# ESP32.net
KiCad netlist of a schematic drawn in EAGLE
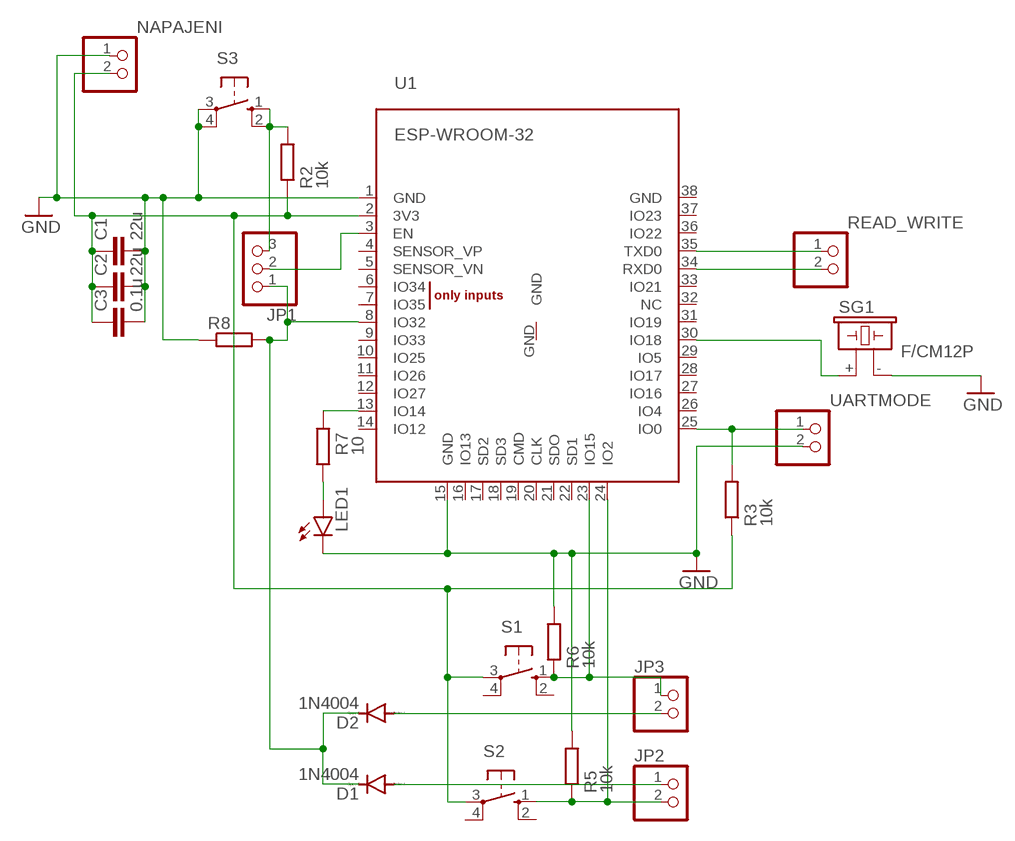
[diagram p0: schematic, sheet 1]

(export (version "E")
  (design (tool "Eeschema 10.0.6"))
  (components
    (comp (ref "C1")
      (value "22u")
      (footprint "eagle-import:C2.5-2")
      (libsource (lib "eagle-import") (part "C2.5/2"))
    )
    (comp (ref "C2")
      (value "22u")
      (footprint "eagle-import:C2.5-2")
      (libsource (lib "eagle-import") (part "C2.5/2"))
    )
    (comp (ref "C3")
      (value "0.1u")
      (footprint "eagle-import:C2.5-2")
      (libsource (lib "eagle-import") (part "C2.5/2"))
    )
    (comp (ref "D1")
      (value "1N4004")
      (footprint "eagle-import:DO41-10")
      (libsource (lib "eagle-import") (part "1N4004"))
    )
    (comp (ref "D2")
      (value "1N4004")
      (footprint "eagle-import:DO41-10")
      (libsource (lib "eagle-import") (part "1N4004"))
    )
    (comp (ref "JP1")
      (value "PINHD-1X3")
      (footprint "eagle-import:1X03")
      (libsource (lib "eagle-import") (part "PINHD-1X3"))
    )
    (comp (ref "JP2")
      (value "PINHD-1X2")
      (footprint "eagle-import:1X02")
      (libsource (lib "eagle-import") (part "PINHD-1X2"))
    )
    (comp (ref "JP3")
      (value "PINHD-1X2")
      (footprint "eagle-import:1X02")
      (libsource (lib "eagle-import") (part "PINHD-1X2"))
    )
    (comp (ref "LED1")
      (value "LED5MM")
      (footprint "eagle-import:LED5MM")
      (libsource (lib "eagle-import") (part "LED5MM"))
    )
    (comp (ref "NAPAJENI")
      (value "PINHD-1X2")
      (footprint "eagle-import:1X02")
      (libsource (lib "eagle-import") (part "PINHD-1X2"))
    )
    (comp (ref "R2")
      (value "10k")
      (footprint "eagle-import:0207_10")
      (libsource (lib "eagle-import") (part "R-EU_0207/10"))
    )
    (comp (ref "R3")
      (value "10k")
      (footprint "eagle-import:0207_10")
      (libsource (lib "eagle-import") (part "R-EU_0207/10"))
    )
    (comp (ref "R5")
      (value "10k")
      (footprint "eagle-import:0207_10")
      (libsource (lib "eagle-import") (part "R-EU_0207/10"))
    )
    (comp (ref "R6")
      (value "10k")
      (footprint "eagle-import:0207_10")
      (libsource (lib "eagle-import") (part "R-EU_0207/10"))
    )
    (comp (ref "R7")
      (value "10")
      (footprint "eagle-import:0207_10")
      (libsource (lib "eagle-import") (part "R-EU_0207/10"))
    )
    (comp (ref "R8")
      (value "R-EU_0207/10")
      (footprint "eagle-import:0207_10")
      (libsource (lib "eagle-import") (part "R-EU_0207/10"))
    )
    (comp (ref "READ_WRITE")
      (value "PINHD-1X2")
      (footprint "eagle-import:1X02")
      (libsource (lib "eagle-import") (part "PINHD-1X2"))
    )
    (comp (ref "S1")
      (value "10-XX")
      (footprint "eagle-import:B3F-10XX")
      (fields (field (name "MPN") "B3F-1000"))
      (libsource (lib "eagle-import") (part "10-XX"))
    )
    (comp (ref "S2")
      (value "10-XX")
      (footprint "eagle-import:B3F-10XX")
      (fields (field (name "MPN") "B3F-1000"))
      (libsource (lib "eagle-import") (part "10-XX"))
    )
    (comp (ref "S3")
      (value "10-XX")
      (footprint "eagle-import:B3F-10XX")
      (fields (field (name "MPN") "B3F-1000"))
      (libsource (lib "eagle-import") (part "10-XX"))
    )
    (comp (ref "SG1")
      (value "F/CM12P")
      (footprint "eagle-import:F_CM12P")
      (libsource (lib "eagle-import") (part "F/CM12P"))
    )
    (comp (ref "U1")
      (value "ESP-WROOM-32")
      (footprint "eagle-import:ESP-WROOM-32")
      (libsource (lib "eagle-import") (part "ESP-WROOM-32"))
    )
    (comp (ref "UARTMODE")
      (value "PINHD-1X2")
      (footprint "eagle-import:1X02")
      (libsource (lib "eagle-import") (part "PINHD-1X2"))
    )
  )
  (nets
    (net (code "1") (name "GND") (class "Default")
      (node (ref "C1") (pin "2") (pinfunction "2_2") (pintype "passive"))
      (node (ref "C2") (pin "2") (pinfunction "2_2") (pintype "passive"))
      (node (ref "C3") (pin "2") (pinfunction "2_2") (pintype "passive"))
      (node (ref "LED1") (pin "K") (pinfunction "C_K") (pintype "passive"))
      (node (ref "NAPAJENI") (pin "1") (pinfunction "1_1") (pintype "passive"))
      (node (ref "R5") (pin "2") (pinfunction "2_2") (pintype "passive"))
      (node (ref "R6") (pin "2") (pinfunction "2_2") (pintype "passive"))
      (node (ref "R8") (pin "1") (pinfunction "1_1") (pintype "passive"))
      (node (ref "S3") (pin "3") (pinfunction "P_3") (pintype "passive"))
      (node (ref "S3") (pin "4") (pinfunction "P1_4") (pintype "passive"))
      (node (ref "SG1") (pin "-") (pinfunction "2_-") (pintype "passive"))
      (node (ref "U1") (pin "1") (pinfunction "GND_1") (pintype "bidirectional"))
      (node (ref "U1") (pin "15") (pinfunction "GND_15") (pintype "bidirectional"))
      (node (ref "UARTMODE") (pin "2") (pinfunction "2_2") (pintype "passive"))
    )
    (net (code "2") (name "Net-(D1-PadA)") (class "Default")
      (node (ref "D1") (pin "A") (pinfunction "A_A") (pintype "passive"))
      (node (ref "JP2") (pin "1") (pinfunction "1_1") (pintype "passive"))
    )
    (net (code "3") (name "Net-(D2-PadA)") (class "Default")
      (node (ref "D2") (pin "A") (pinfunction "A_A") (pintype "passive"))
      (node (ref "JP3") (pin "2") (pinfunction "2_2") (pintype "passive"))
    )
    (net (code "4") (name "Net-(LED1-PadA)") (class "Default")
      (node (ref "LED1") (pin "A") (pinfunction "A_A") (pintype "passive"))
      (node (ref "R7") (pin "1") (pinfunction "1_1") (pintype "passive"))
    )
    (net (code "5") (name "Net-(S1-P)") (class "Default")
      (node (ref "C1") (pin "1") (pinfunction "1_1") (pintype "passive"))
      (node (ref "C2") (pin "1") (pinfunction "1_1") (pintype "passive"))
      (node (ref "C3") (pin "1") (pinfunction "1_1") (pintype "passive"))
      (node (ref "NAPAJENI") (pin "2") (pinfunction "2_2") (pintype "passive"))
      (node (ref "R2") (pin "1") (pinfunction "1_1") (pintype "passive"))
      (node (ref "R3") (pin "1") (pinfunction "1_1") (pintype "passive"))
      (node (ref "S1") (pin "3") (pinfunction "P_3") (pintype "passive"))
      (node (ref "S2") (pin "3") (pinfunction "P_3") (pintype "passive"))
      (node (ref "U1") (pin "2") (pinfunction "3V3_2") (pintype "bidirectional"))
    )
    (net (code "6") (name "Net-(S1-S)") (class "Default")
      (node (ref "JP3") (pin "1") (pinfunction "1_1") (pintype "passive"))
      (node (ref "R6") (pin "1") (pinfunction "1_1") (pintype "passive"))
      (node (ref "S1") (pin "1") (pinfunction "S_1") (pintype "passive"))
      (node (ref "U1") (pin "23") (pinfunction "IO15_23") (pintype "bidirectional"))
    )
    (net (code "7") (name "Net-(S2-S)") (class "Default")
      (node (ref "JP2") (pin "2") (pinfunction "2_2") (pintype "passive"))
      (node (ref "R5") (pin "1") (pinfunction "1_1") (pintype "passive"))
      (node (ref "S2") (pin "1") (pinfunction "S_1") (pintype "passive"))
      (node (ref "U1") (pin "24") (pinfunction "IO2_24") (pintype "bidirectional"))
    )
    (net (code "8") (name "Net-(S3-S)") (class "Default")
      (node (ref "JP1") (pin "3") (pinfunction "3_3") (pintype "passive"))
      (node (ref "R2") (pin "2") (pinfunction "2_2") (pintype "passive"))
      (node (ref "S3") (pin "1") (pinfunction "S_1") (pintype "passive"))
      (node (ref "S3") (pin "2") (pinfunction "S1_2") (pintype "passive"))
    )
    (net (code "9") (name "Net-(SG1-1)") (class "Default")
      (node (ref "SG1") (pin "+") (pinfunction "1_+") (pintype "passive"))
      (node (ref "U1") (pin "30") (pinfunction "IO18_30") (pintype "bidirectional"))
    )
    (net (code "10") (name "Net-(U1-EN)") (class "Default")
      (node (ref "JP1") (pin "2") (pinfunction "2_2") (pintype "passive"))
      (node (ref "U1") (pin "3") (pinfunction "EN_3") (pintype "bidirectional"))
    )
    (net (code "11") (name "Net-(U1-IO0)") (class "Default")
      (node (ref "R3") (pin "2") (pinfunction "2_2") (pintype "passive"))
      (node (ref "U1") (pin "25") (pinfunction "IO0_25") (pintype "bidirectional"))
      (node (ref "UARTMODE") (pin "1") (pinfunction "1_1") (pintype "passive"))
    )
    (net (code "12") (name "Net-(U1-IO14)") (class "Default")
      (node (ref "R7") (pin "2") (pinfunction "2_2") (pintype "passive"))
      (node (ref "U1") (pin "13") (pinfunction "IO14_13") (pintype "bidirectional"))
    )
    (net (code "13") (name "Net-(U1-IO32)") (class "Default")
      (node (ref "D1") (pin "C") (pinfunction "C_C") (pintype "passive"))
      (node (ref "D2") (pin "C") (pinfunction "C_C") (pintype "passive"))
      (node (ref "JP1") (pin "1") (pinfunction "1_1") (pintype "passive"))
      (node (ref "R8") (pin "2") (pinfunction "2_2") (pintype "passive"))
      (node (ref "U1") (pin "8") (pinfunction "IO32_8") (pintype "bidirectional"))
    )
    (net (code "14") (name "Net-(U1-RXD0)") (class "Default")
      (node (ref "READ_WRITE") (pin "2") (pinfunction "2_2") (pintype "passive"))
      (node (ref "U1") (pin "34") (pinfunction "RXD0_34") (pintype "bidirectional"))
    )
    (net (code "15") (name "Net-(U1-TXD0)") (class "Default")
      (node (ref "READ_WRITE") (pin "1") (pinfunction "1_1") (pintype "passive"))
      (node (ref "U1") (pin "35") (pinfunction "TXD0_35") (pintype "bidirectional"))
    )
    (net (code "16") (name "unconnected-(S1-P1-Pad4)") (class "Default")
      (node (ref "S1") (pin "4") (pinfunction "P1_4") (pintype "passive"))
    )
    (net (code "17") (name "unconnected-(S1-S1-Pad2)") (class "Default")
      (node (ref "S1") (pin "2") (pinfunction "S1_2") (pintype "passive"))
    )
    (net (code "18") (name "unconnected-(S2-P1-Pad4)") (class "Default")
      (node (ref "S2") (pin "4") (pinfunction "P1_4") (pintype "passive"))
    )
    (net (code "19") (name "unconnected-(S2-S1-Pad2)") (class "Default")
      (node (ref "S2") (pin "2") (pinfunction "S1_2") (pintype "passive"))
    )
    (net (code "20") (name "unconnected-(U1-CLK-Pad20)") (class "Default")
      (node (ref "U1") (pin "20") (pinfunction "CLK_20") (pintype "bidirectional"))
    )
    (net (code "21") (name "unconnected-(U1-CMD-Pad19)") (class "Default")
      (node (ref "U1") (pin "19") (pinfunction "CMD_19") (pintype "bidirectional"))
    )
    (net (code "22") (name "unconnected-(U1-GND-Pad38)") (class "Default")
      (node (ref "U1") (pin "38") (pinfunction "GND_38") (pintype "bidirectional"))
    )
    (net (code "23") (name "unconnected-(U1-IO4-Pad26)") (class "Default")
      (node (ref "U1") (pin "26") (pinfunction "IO4_26") (pintype "bidirectional"))
    )
    (net (code "24") (name "unconnected-(U1-IO5-Pad29)") (class "Default")
      (node (ref "U1") (pin "29") (pinfunction "IO5_29") (pintype "bidirectional"))
    )
    (net (code "25") (name "unconnected-(U1-IO12-Pad14)") (class "Default")
      (node (ref "U1") (pin "14") (pinfunction "IO12_14") (pintype "bidirectional"))
    )
    (net (code "26") (name "unconnected-(U1-IO13-Pad16)") (class "Default")
      (node (ref "U1") (pin "16") (pinfunction "IO13_16") (pintype "bidirectional"))
    )
    (net (code "27") (name "unconnected-(U1-IO16-Pad27)") (class "Default")
      (node (ref "U1") (pin "27") (pinfunction "IO16_27") (pintype "bidirectional"))
    )
    (net (code "28") (name "unconnected-(U1-IO17-Pad28)") (class "Default")
      (node (ref "U1") (pin "28") (pinfunction "IO17_28") (pintype "bidirectional"))
    )
    (net (code "29") (name "unconnected-(U1-IO19-Pad31)") (class "Default")
      (node (ref "U1") (pin "31") (pinfunction "IO19_31") (pintype "bidirectional"))
    )
    (net (code "30") (name "unconnected-(U1-IO21-Pad33)") (class "Default")
      (node (ref "U1") (pin "33") (pinfunction "IO21_33") (pintype "bidirectional"))
    )
    (net (code "31") (name "unconnected-(U1-IO22-Pad36)") (class "Default")
      (node (ref "U1") (pin "36") (pinfunction "IO22_36") (pintype "bidirectional"))
    )
    (net (code "32") (name "unconnected-(U1-IO23-Pad37)") (class "Default")
      (node (ref "U1") (pin "37") (pinfunction "IO23_37") (pintype "bidirectional"))
    )
    (net (code "33") (name "unconnected-(U1-IO25-Pad10)") (class "Default")
      (node (ref "U1") (pin "10") (pinfunction "IO25_10") (pintype "bidirectional"))
    )
    (net (code "34") (name "unconnected-(U1-IO26-Pad11)") (class "Default")
      (node (ref "U1") (pin "11") (pinfunction "IO26_11") (pintype "bidirectional"))
    )
    (net (code "35") (name "unconnected-(U1-IO27-Pad12)") (class "Default")
      (node (ref "U1") (pin "12") (pinfunction "IO27_12") (pintype "bidirectional"))
    )
    (net (code "36") (name "unconnected-(U1-IO33-Pad9)") (class "Default")
      (node (ref "U1") (pin "9") (pinfunction "IO33_9") (pintype "bidirectional"))
    )
    (net (code "37") (name "unconnected-(U1-IO34-Pad6)") (class "Default")
      (node (ref "U1") (pin "6") (pinfunction "IO34_6") (pintype "input"))
    )
    (net (code "38") (name "unconnected-(U1-IO35-Pad7)") (class "Default")
      (node (ref "U1") (pin "7") (pinfunction "IO35_7") (pintype "input"))
    )
    (net (code "39") (name "unconnected-(U1-NC-Pad32)") (class "Default")
      (node (ref "U1") (pin "32") (pinfunction "NC_32") (pintype "bidirectional"))
    )
    (net (code "40") (name "unconnected-(U1-PadGND)") (class "Default")
      (node (ref "U1") (pin "GND") (pinfunction "GND_GND") (pintype "bidirectional"))
    )
    (net (code "41") (name "unconnected-(U1-SD1-Pad22)") (class "Default")
      (node (ref "U1") (pin "22") (pinfunction "SD1_22") (pintype "bidirectional"))
    )
    (net (code "42") (name "unconnected-(U1-SD2-Pad17)") (class "Default")
      (node (ref "U1") (pin "17") (pinfunction "SD2_17") (pintype "bidirectional"))
    )
    (net (code "43") (name "unconnected-(U1-SD3-Pad18)") (class "Default")
      (node (ref "U1") (pin "18") (pinfunction "SD3_18") (pintype "bidirectional"))
    )
    (net (code "44") (name "unconnected-(U1-SDO-Pad21)") (class "Default")
      (node (ref "U1") (pin "21") (pinfunction "SDO_21") (pintype "bidirectional"))
    )
    (net (code "45") (name "unconnected-(U1-SENSOR_VN-Pad5)") (class "Default")
      (node (ref "U1") (pin "5") (pinfunction "SENSOR_VN_5") (pintype "input"))
    )
    (net (code "46") (name "unconnected-(U1-SENSOR_VP-Pad4)") (class "Default")
      (node (ref "U1") (pin "4") (pinfunction "SENSOR_VP_4") (pintype "input"))
    )
  )
)
